# Review_PCD_1_8.net
KiCad netlist of a schematic drawn in EAGLE
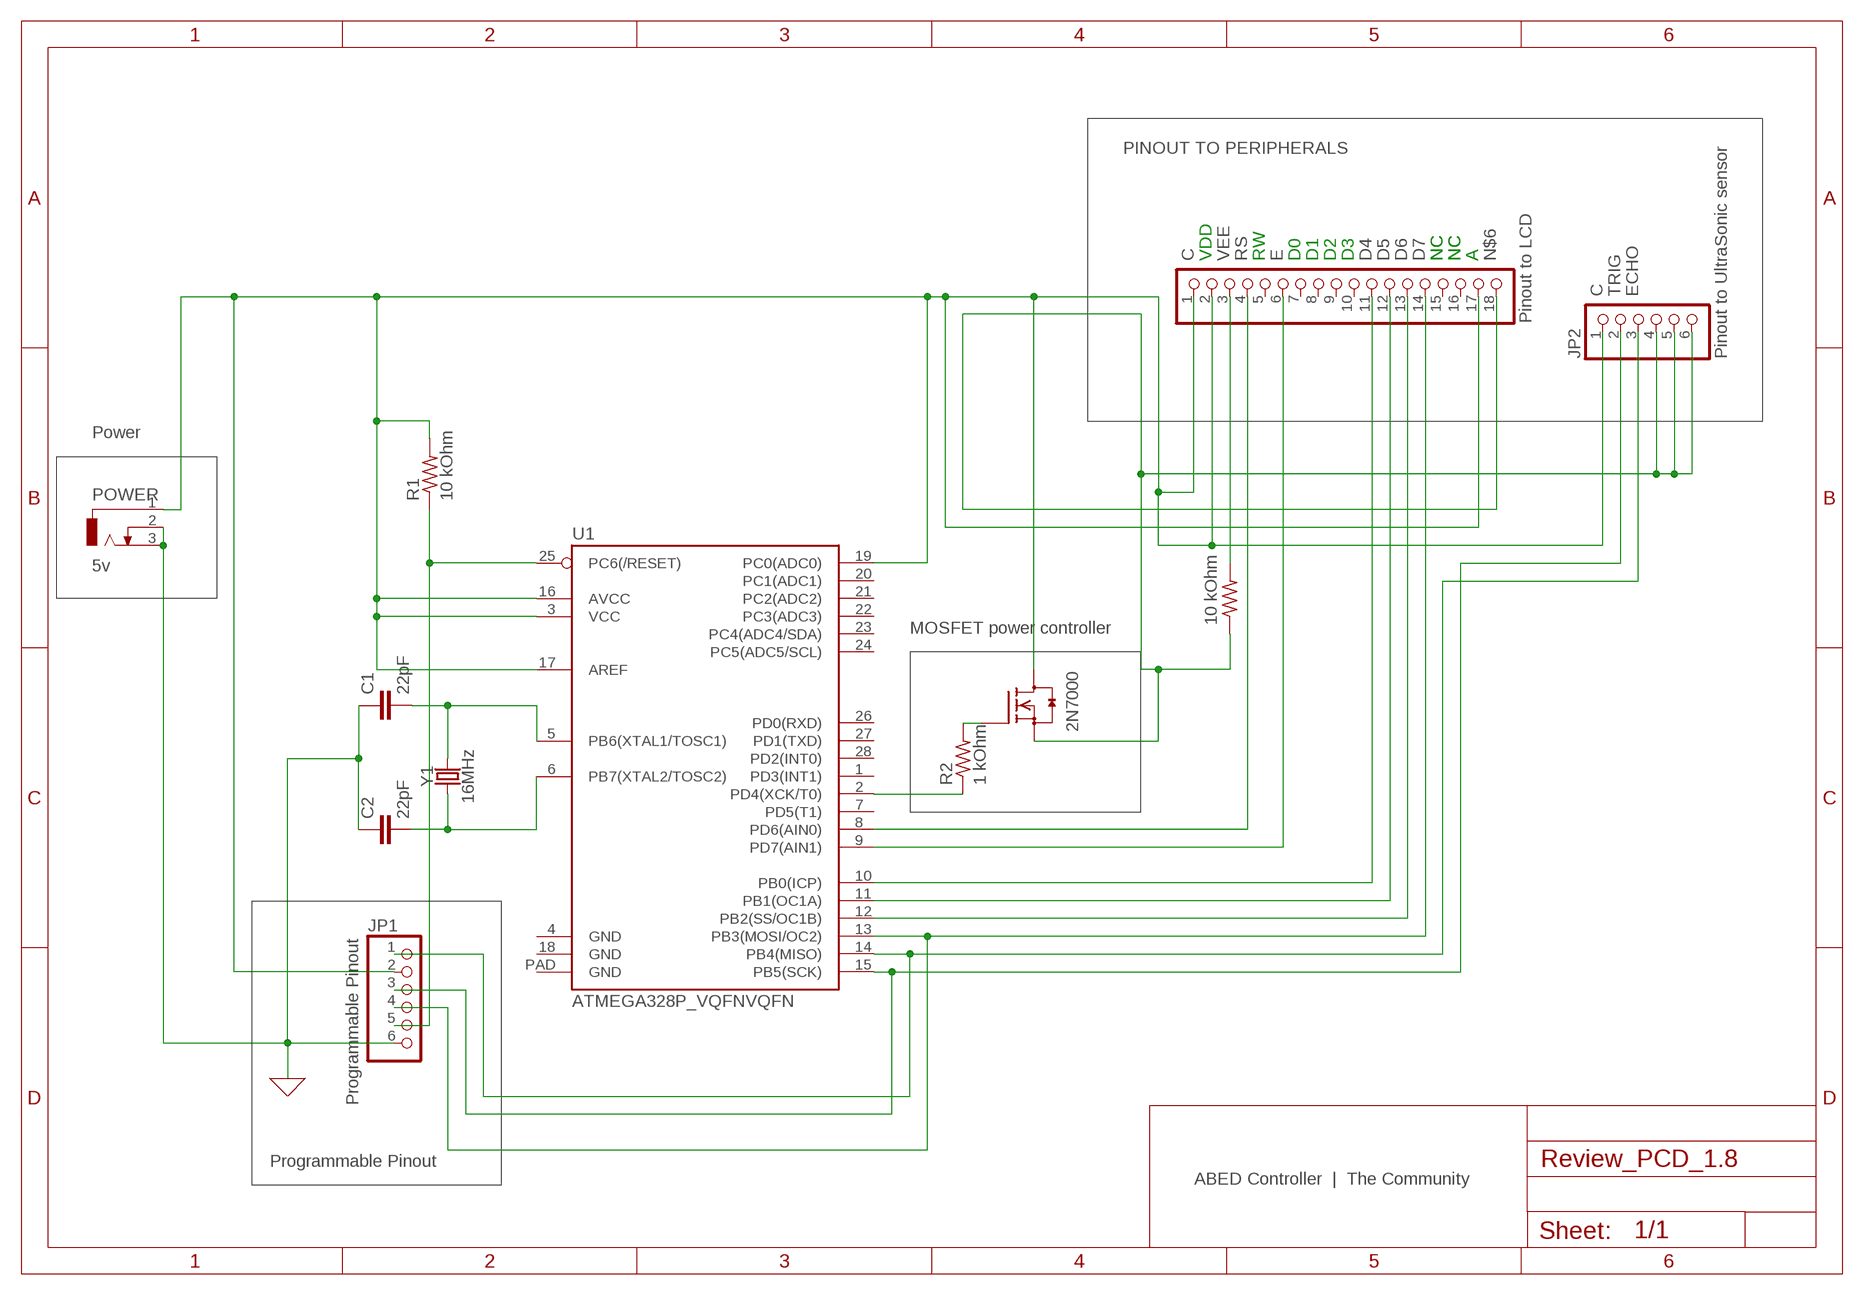
[diagram p0: schematic, sheet 1]

(export (version "E")
  (design (tool "Eeschema 10.0.6"))
  (components
    (comp (ref "C1")
      (value "22pF")
      (footprint "eagle-import:CAP-PTH-2.54")
      (libsource (lib "eagle-import") (part "22PF-PTH-2.54MM-200V-5%"))
    )
    (comp (ref "C2")
      (value "22pF")
      (footprint "eagle-import:CAP-PTH-2.54")
      (libsource (lib "eagle-import") (part "22PF-PTH-2.54MM-200V-5%"))
    )
    (comp (ref "JP1")
      (value "Programmable Pinout")
      (footprint "eagle-import:1X06-3.5MM")
      (libsource (lib "eagle-import") (part "PINHD-1X6-3.5MM"))
    )
    (comp (ref "JP2")
      (value "Pinout to UltraSonic sensor")
      (footprint "eagle-import:1X06-BIG")
      (libsource (lib "eagle-import") (part "PINHD-1X6B"))
    )
    (comp (ref "JP3")
      (value "Pinout to LCD")
      (footprint "eagle-import:1X18")
      (libsource (lib "eagle-import") (part "PINHD-1X18"))
    )
    (comp (ref "POWER")
      (value "5v")
      (footprint "eagle-import:DCJ0202")
      (libsource (lib "eagle-import") (part "DCJ0202"))
    )
    (comp (ref "Q2")
      (value "2N7000")
      (footprint "eagle-import:TO92")
      (libsource (lib "eagle-import") (part "2N7000KL/BS170KL"))
    )
    (comp (ref "R1")
      (value "10 kOhm")
      (footprint "eagle-import:R2012W")
      (libsource (lib "eagle-import") (part "R-US_R2012W"))
    )
    (comp (ref "R2")
      (value "1 kOhm")
      (footprint "eagle-import:R2012W")
      (fields (field (name "R1") "1 kOhm"))
      (libsource (lib "eagle-import") (part "R-US_R2012W"))
    )
    (comp (ref "R3")
      (value "10 kOhm")
      (footprint "eagle-import:R2012W")
      (fields (field (name "R1") "10 kOhm"))
      (libsource (lib "eagle-import") (part "R-US_R2012W"))
    )
    (comp (ref "U1")
      (value "ATMEGA328P_VQFNVQFN")
      (footprint "eagle-import:VQFN-28")
      (libsource (lib "eagle-import") (part "ATMEGA328P_VQFNVQFN"))
    )
    (comp (ref "Y1")
      (value "16MHz")
      (footprint "eagle-import:HC49US")
      (libsource (lib "eagle-import") (part "CRYSTAL-16MHZPTH-HC49US"))
    )
  )
  (nets
    (net (code "1") (name "/C") (class "Default")
      (node (ref "JP1") (pin "2") (pinfunction "2_2") (pintype "passive"))
      (node (ref "JP2") (pin "1") (pinfunction "1_1") (pintype "passive"))
      (node (ref "JP3") (pin "1") (pinfunction "1_1") (pintype "passive"))
      (node (ref "JP3") (pin "17") (pinfunction "17_17") (pintype "passive"))
      (node (ref "JP3") (pin "2") (pinfunction "2_2") (pintype "passive"))
      (node (ref "POWER") (pin "1") (pinfunction "1_1") (pintype "passive"))
      (node (ref "Q2") (pin "3") (pinfunction "D_3") (pintype "passive"))
      (node (ref "R1") (pin "2") (pinfunction "2_2") (pintype "passive"))
      (node (ref "U1") (pin "16") (pinfunction "AVCC_16") (pintype "bidirectional"))
      (node (ref "U1") (pin "17") (pinfunction "AREF_17") (pintype "bidirectional"))
      (node (ref "U1") (pin "19") (pinfunction "PC0(ADC0)_19") (pintype "bidirectional"))
      (node (ref "U1") (pin "3") (pinfunction "VCC_3") (pintype "bidirectional"))
    )
    (net (code "2") (name "/D4") (class "Default")
      (node (ref "JP3") (pin "11") (pinfunction "11_11") (pintype "passive"))
      (node (ref "U1") (pin "10") (pinfunction "PB0(ICP)_10") (pintype "bidirectional"))
    )
    (net (code "3") (name "/D5") (class "Default")
      (node (ref "JP3") (pin "12") (pinfunction "12_12") (pintype "passive"))
      (node (ref "U1") (pin "11") (pinfunction "PB1(OC1A)_11") (pintype "bidirectional"))
    )
    (net (code "4") (name "/D6") (class "Default")
      (node (ref "JP3") (pin "13") (pinfunction "13_13") (pintype "passive"))
      (node (ref "U1") (pin "12") (pinfunction "PB2(SS/OC1B)_12") (pintype "bidirectional"))
    )
    (net (code "5") (name "/D7") (class "Default")
      (node (ref "JP1") (pin "4") (pinfunction "4_4") (pintype "passive"))
      (node (ref "JP3") (pin "14") (pinfunction "14_14") (pintype "passive"))
      (node (ref "U1") (pin "13") (pinfunction "PB3(MOSI/OC2)_13") (pintype "bidirectional"))
    )
    (net (code "6") (name "/E") (class "Default")
      (node (ref "JP3") (pin "6") (pinfunction "6_6") (pintype "passive"))
      (node (ref "U1") (pin "9") (pinfunction "PD7(AIN1)_9") (pintype "bidirectional"))
    )
    (net (code "7") (name "/ECHO") (class "Default")
      (node (ref "JP1") (pin "1") (pinfunction "1_1") (pintype "passive"))
      (node (ref "JP2") (pin "3") (pinfunction "3_3") (pintype "passive"))
      (node (ref "U1") (pin "14") (pinfunction "PB4(MISO)_14") (pintype "bidirectional"))
    )
    (net (code "8") (name "/N$6") (class "Default")
      (node (ref "JP2") (pin "4") (pinfunction "4_4") (pintype "passive"))
      (node (ref "JP2") (pin "5") (pinfunction "5_5") (pintype "passive"))
      (node (ref "JP2") (pin "6") (pinfunction "6_6") (pintype "passive"))
      (node (ref "JP3") (pin "18") (pinfunction "18_18") (pintype "passive"))
      (node (ref "Q2") (pin "1") (pinfunction "S_1") (pintype "passive"))
      (node (ref "R3") (pin "1") (pinfunction "1_1") (pintype "passive"))
    )
    (net (code "9") (name "/RS") (class "Default")
      (node (ref "JP3") (pin "4") (pinfunction "4_4") (pintype "passive"))
      (node (ref "U1") (pin "8") (pinfunction "PD6(AIN0)_8") (pintype "bidirectional"))
    )
    (net (code "10") (name "/TRIG") (class "Default")
      (node (ref "JP1") (pin "3") (pinfunction "3_3") (pintype "passive"))
      (node (ref "JP2") (pin "2") (pinfunction "2_2") (pintype "passive"))
      (node (ref "U1") (pin "15") (pinfunction "PB5(SCK)_15") (pintype "bidirectional"))
    )
    (net (code "11") (name "/VEE") (class "Default")
      (node (ref "JP3") (pin "3") (pinfunction "3_3") (pintype "passive"))
      (node (ref "R3") (pin "2") (pinfunction "2_2") (pintype "passive"))
    )
    (net (code "12") (name "GND") (class "Default")
      (node (ref "C1") (pin "1") (pinfunction "1_1") (pintype "passive"))
      (node (ref "C2") (pin "1") (pinfunction "1_1") (pintype "passive"))
      (node (ref "JP1") (pin "6") (pinfunction "6_6") (pintype "passive"))
      (node (ref "POWER") (pin "2") (pinfunction "2_2") (pintype "passive"))
      (node (ref "POWER") (pin "3") (pinfunction "3_3") (pintype "passive"))
    )
    (net (code "13") (name "Net-(Q2-G)") (class "Default")
      (node (ref "Q2") (pin "2") (pinfunction "G_2") (pintype "passive"))
      (node (ref "R2") (pin "2") (pinfunction "2_2") (pintype "passive"))
    )
    (net (code "14") (name "Net-(U1-PB6(XTAL1{slash}TOSC1))") (class "Default")
      (node (ref "C1") (pin "2") (pinfunction "2_2") (pintype "passive"))
      (node (ref "U1") (pin "5") (pinfunction "PB6(XTAL1/TOSC1)_5") (pintype "bidirectional"))
      (node (ref "Y1") (pin "2") (pinfunction "2_2") (pintype "passive"))
    )
    (net (code "15") (name "Net-(U1-PB7(XTAL2{slash}TOSC2))") (class "Default")
      (node (ref "C2") (pin "2") (pinfunction "2_2") (pintype "passive"))
      (node (ref "U1") (pin "6") (pinfunction "PB7(XTAL2/TOSC2)_6") (pintype "bidirectional"))
      (node (ref "Y1") (pin "1") (pinfunction "1_1") (pintype "passive"))
    )
    (net (code "16") (name "Net-(U1-PC6({slash}RESET))") (class "Default")
      (node (ref "JP1") (pin "5") (pinfunction "5_5") (pintype "passive"))
      (node (ref "R1") (pin "1") (pinfunction "1_1") (pintype "passive"))
      (node (ref "U1") (pin "25") (pinfunction "PC6(/RESET)_25") (pintype "bidirectional"))
    )
    (net (code "17") (name "Net-(U1-PD4(XCK{slash}T0))") (class "Default")
      (node (ref "R2") (pin "1") (pinfunction "1_1") (pintype "passive"))
      (node (ref "U1") (pin "2") (pinfunction "PD4(XCK/T0)_2") (pintype "bidirectional"))
    )
    (net (code "18") (name "unconnected-(JP3-Pad5)") (class "Default")
      (node (ref "JP3") (pin "5") (pinfunction "5_5") (pintype "passive"))
    )
    (net (code "19") (name "unconnected-(JP3-Pad7)") (class "Default")
      (node (ref "JP3") (pin "7") (pinfunction "7_7") (pintype "passive"))
    )
    (net (code "20") (name "unconnected-(JP3-Pad8)") (class "Default")
      (node (ref "JP3") (pin "8") (pinfunction "8_8") (pintype "passive"))
    )
    (net (code "21") (name "unconnected-(JP3-Pad9)") (class "Default")
      (node (ref "JP3") (pin "9") (pinfunction "9_9") (pintype "passive"))
    )
    (net (code "22") (name "unconnected-(JP3-Pad10)") (class "Default")
      (node (ref "JP3") (pin "10") (pinfunction "10_10") (pintype "passive"))
    )
    (net (code "23") (name "unconnected-(JP3-Pad15)") (class "Default")
      (node (ref "JP3") (pin "15") (pinfunction "15_15") (pintype "passive"))
    )
    (net (code "24") (name "unconnected-(JP3-Pad16)") (class "Default")
      (node (ref "JP3") (pin "16") (pinfunction "16_16") (pintype "passive"))
    )
    (net (code "25") (name "unconnected-(U1-GND-Pad4)") (class "Default")
      (node (ref "U1") (pin "4") (pinfunction "GND_4") (pintype "bidirectional"))
    )
    (net (code "26") (name "unconnected-(U1-GND-Pad18)") (class "Default")
      (node (ref "U1") (pin "18") (pinfunction "GND_18") (pintype "bidirectional"))
    )
    (net (code "27") (name "unconnected-(U1-GND-PadPAD)") (class "Default")
      (node (ref "U1") (pin "PAD") (pinfunction "GND_PAD") (pintype "bidirectional"))
    )
    (net (code "28") (name "unconnected-(U1-PC1(ADC1)-Pad20)") (class "Default")
      (node (ref "U1") (pin "20") (pinfunction "PC1(ADC1)_20") (pintype "bidirectional"))
    )
    (net (code "29") (name "unconnected-(U1-PC2(ADC2)-Pad21)") (class "Default")
      (node (ref "U1") (pin "21") (pinfunction "PC2(ADC2)_21") (pintype "bidirectional"))
    )
    (net (code "30") (name "unconnected-(U1-PC3(ADC3)-Pad22)") (class "Default")
      (node (ref "U1") (pin "22") (pinfunction "PC3(ADC3)_22") (pintype "bidirectional"))
    )
    (net (code "31") (name "unconnected-(U1-PC4(ADC4{slash}SDA)-Pad23)") (class "Default")
      (node (ref "U1") (pin "23") (pinfunction "PC4(ADC4/SDA)_23") (pintype "bidirectional"))
    )
    (net (code "32") (name "unconnected-(U1-PC5(ADC5{slash}SCL)-Pad24)") (class "Default")
      (node (ref "U1") (pin "24") (pinfunction "PC5(ADC5/SCL)_24") (pintype "bidirectional"))
    )
    (net (code "33") (name "unconnected-(U1-PD0(RXD)-Pad26)") (class "Default")
      (node (ref "U1") (pin "26") (pinfunction "PD0(RXD)_26") (pintype "bidirectional"))
    )
    (net (code "34") (name "unconnected-(U1-PD1(TXD)-Pad27)") (class "Default")
      (node (ref "U1") (pin "27") (pinfunction "PD1(TXD)_27") (pintype "bidirectional"))
    )
    (net (code "35") (name "unconnected-(U1-PD2(INT0)-Pad28)") (class "Default")
      (node (ref "U1") (pin "28") (pinfunction "PD2(INT0)_28") (pintype "bidirectional"))
    )
    (net (code "36") (name "unconnected-(U1-PD3(INT1)-Pad1)") (class "Default")
      (node (ref "U1") (pin "1") (pinfunction "PD3(INT1)_1") (pintype "bidirectional"))
    )
    (net (code "37") (name "unconnected-(U1-PD5(T1)-Pad7)") (class "Default")
      (node (ref "U1") (pin "7") (pinfunction "PD5(T1)_7") (pintype "bidirectional"))
    )
  )
)
